# FlatSat-PC-104.net
KiCad netlist of a schematic drawn in Altium Designer
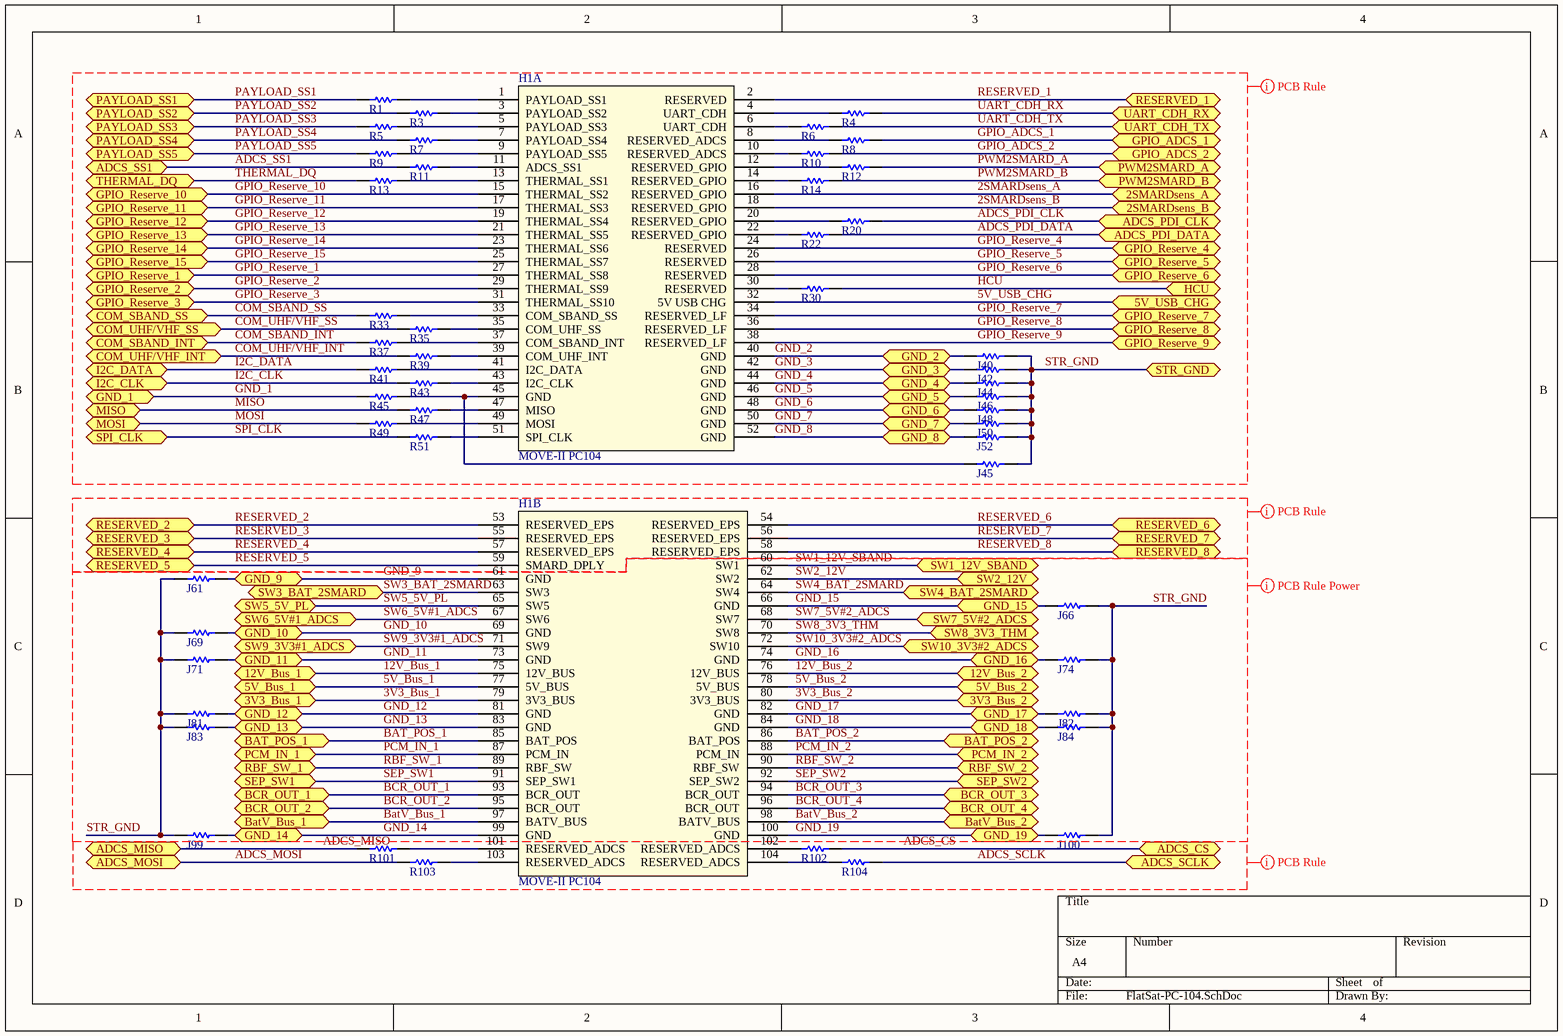
[diagram p0: FlatSat-PC-104.SchDoc]

(export (version "E")
  (design (tool "Eeschema 10.0.6"))
  (components
    (comp (ref "H1")
      (value "MOVE-II PC104")
      (footprint "EPS")
      (libsource (lib "MOVE-II") (part "MOVE-II PC104"))
    )
    (comp (ref "J40")
      (value "CRCW06030000Z0EA")
      (footprint "RESC1609X55X30ML10T20")
      (fields (field (name "MANUFACTURER") "Vishay Dale"))
      (libsource (lib "Altium Content Vault") (part "CMP-2000-03816-1"))
    )
    (comp (ref "J42")
      (value "CRCW06030000Z0EA")
      (footprint "RESC1609X55X30ML10T20")
      (fields (field (name "MANUFACTURER") "Vishay Dale"))
      (libsource (lib "Altium Content Vault") (part "CMP-2000-03816-1"))
    )
    (comp (ref "J44")
      (value "CRCW06030000Z0EA")
      (footprint "RESC1609X55X30ML10T20")
      (fields (field (name "MANUFACTURER") "Vishay Dale"))
      (libsource (lib "Altium Content Vault") (part "CMP-2000-03816-1"))
    )
    (comp (ref "J45")
      (value "CRCW06030000Z0EA")
      (footprint "RESC1609X55X30ML10T20")
      (fields (field (name "MANUFACTURER") "Vishay Dale"))
      (libsource (lib "Altium Content Vault") (part "CMP-2000-03816-1"))
    )
    (comp (ref "J46")
      (value "CRCW06030000Z0EA")
      (footprint "RESC1609X55X30ML10T20")
      (fields (field (name "MANUFACTURER") "Vishay Dale"))
      (libsource (lib "Altium Content Vault") (part "CMP-2000-03816-1"))
    )
    (comp (ref "J48")
      (value "CRCW06030000Z0EA")
      (footprint "RESC1609X55X30ML10T20")
      (fields (field (name "MANUFACTURER") "Vishay Dale"))
      (libsource (lib "Altium Content Vault") (part "CMP-2000-03816-1"))
    )
    (comp (ref "J50")
      (value "CRCW06030000Z0EA")
      (footprint "RESC1609X55X30ML10T20")
      (fields (field (name "MANUFACTURER") "Vishay Dale"))
      (libsource (lib "Altium Content Vault") (part "CMP-2000-03816-1"))
    )
    (comp (ref "J52")
      (value "CRCW06030000Z0EA")
      (footprint "RESC1609X55X30ML10T20")
      (fields (field (name "MANUFACTURER") "Vishay Dale"))
      (libsource (lib "Altium Content Vault") (part "CMP-2000-03816-1"))
    )
    (comp (ref "J61")
      (value "CRCW06030000Z0EA")
      (footprint "RESC1609X55X30ML10T20")
      (fields (field (name "MANUFACTURER") "Vishay Dale"))
      (libsource (lib "Altium Content Vault") (part "CMP-2000-03816-1"))
    )
    (comp (ref "J66")
      (value "CRCW06030000Z0EA")
      (footprint "RESC1609X55X30ML10T20")
      (fields (field (name "MANUFACTURER") "Vishay Dale"))
      (libsource (lib "Altium Content Vault") (part "CMP-2000-03816-1"))
    )
    (comp (ref "J69")
      (value "CRCW06030000Z0EA")
      (footprint "RESC1609X55X30ML10T20")
      (fields (field (name "MANUFACTURER") "Vishay Dale"))
      (libsource (lib "Altium Content Vault") (part "CMP-2000-03816-1"))
    )
    (comp (ref "J71")
      (value "CRCW06030000Z0EA")
      (footprint "RESC1609X55X30ML10T20")
      (fields (field (name "MANUFACTURER") "Vishay Dale"))
      (libsource (lib "Altium Content Vault") (part "CMP-2000-03816-1"))
    )
    (comp (ref "J74")
      (value "CRCW06030000Z0EA")
      (footprint "RESC1609X55X30ML10T20")
      (fields (field (name "MANUFACTURER") "Vishay Dale"))
      (libsource (lib "Altium Content Vault") (part "CMP-2000-03816-1"))
    )
    (comp (ref "J81")
      (value "CRCW06030000Z0EA")
      (footprint "RESC1609X55X30ML10T20")
      (fields (field (name "MANUFACTURER") "Vishay Dale"))
      (libsource (lib "Altium Content Vault") (part "CMP-2000-03816-1"))
    )
    (comp (ref "J82")
      (value "CRCW06030000Z0EA")
      (footprint "RESC1609X55X30ML10T20")
      (fields (field (name "MANUFACTURER") "Vishay Dale"))
      (libsource (lib "Altium Content Vault") (part "CMP-2000-03816-1"))
    )
    (comp (ref "J83")
      (value "CRCW06030000Z0EA")
      (footprint "RESC1609X55X30ML10T20")
      (fields (field (name "MANUFACTURER") "Vishay Dale"))
      (libsource (lib "Altium Content Vault") (part "CMP-2000-03816-1"))
    )
    (comp (ref "J84")
      (value "CRCW06030000Z0EA")
      (footprint "RESC1609X55X30ML10T20")
      (fields (field (name "MANUFACTURER") "Vishay Dale"))
      (libsource (lib "Altium Content Vault") (part "CMP-2000-03816-1"))
    )
    (comp (ref "J99")
      (value "CRCW06030000Z0EA")
      (footprint "RESC1609X55X30ML10T20")
      (fields (field (name "MANUFACTURER") "Vishay Dale"))
      (libsource (lib "Altium Content Vault") (part "CMP-2000-03816-1"))
    )
    (comp (ref "J100")
      (value "CRCW06030000Z0EA")
      (footprint "RESC1609X55X30ML10T20")
      (fields (field (name "MANUFACTURER") "Vishay Dale"))
      (libsource (lib "Altium Content Vault") (part "CMP-2000-03816-1"))
    )
    (comp (ref "R1")
      (value "CRCW06030000Z0EA")
      (footprint "RESC1609X55X30ML10T20")
      (fields (field (name "MANUFACTURER") "Vishay Dale"))
      (libsource (lib "Altium Content Vault") (part "CMP-2000-03816-1"))
    )
    (comp (ref "R3")
      (value "CRCW06030000Z0EA")
      (footprint "RESC1609X55X30ML10T20")
      (fields (field (name "MANUFACTURER") "Vishay Dale"))
      (libsource (lib "Altium Content Vault") (part "CMP-2000-03816-1"))
    )
    (comp (ref "R4")
      (value "CRCW06030000Z0EA")
      (footprint "RESC1609X55X30ML10T20")
      (fields (field (name "MANUFACTURER") "Vishay Dale"))
      (libsource (lib "Altium Content Vault") (part "CMP-2000-03816-1"))
    )
    (comp (ref "R5")
      (value "CRCW06030000Z0EA")
      (footprint "RESC1609X55X30ML10T20")
      (fields (field (name "MANUFACTURER") "Vishay Dale"))
      (libsource (lib "Altium Content Vault") (part "CMP-2000-03816-1"))
    )
    (comp (ref "R6")
      (value "CRCW06030000Z0EA")
      (footprint "RESC1609X55X30ML10T20")
      (fields (field (name "MANUFACTURER") "Vishay Dale"))
      (libsource (lib "Altium Content Vault") (part "CMP-2000-03816-1"))
    )
    (comp (ref "R7")
      (value "CRCW06030000Z0EA")
      (footprint "RESC1609X55X30ML10T20")
      (fields (field (name "MANUFACTURER") "Vishay Dale"))
      (libsource (lib "Altium Content Vault") (part "CMP-2000-03816-1"))
    )
    (comp (ref "R8")
      (value "CRCW06030000Z0EA")
      (footprint "RESC1609X55X30ML10T20")
      (fields (field (name "MANUFACTURER") "Vishay Dale"))
      (libsource (lib "Altium Content Vault") (part "CMP-2000-03816-1"))
    )
    (comp (ref "R9")
      (value "CRCW06030000Z0EA")
      (footprint "RESC1609X55X30ML10T20")
      (fields (field (name "MANUFACTURER") "Vishay Dale"))
      (libsource (lib "Altium Content Vault") (part "CMP-2000-03816-1"))
    )
    (comp (ref "R10")
      (value "CRCW06030000Z0EA")
      (footprint "RESC1609X55X30ML10T20")
      (fields (field (name "MANUFACTURER") "Vishay Dale"))
      (libsource (lib "Altium Content Vault") (part "CMP-2000-03816-1"))
    )
    (comp (ref "R11")
      (value "CRCW06030000Z0EA")
      (footprint "RESC1609X55X30ML10T20")
      (fields (field (name "MANUFACTURER") "Vishay Dale"))
      (libsource (lib "Altium Content Vault") (part "CMP-2000-03816-1"))
    )
    (comp (ref "R12")
      (value "CRCW06030000Z0EA")
      (footprint "RESC1609X55X30ML10T20")
      (fields (field (name "MANUFACTURER") "Vishay Dale"))
      (libsource (lib "Altium Content Vault") (part "CMP-2000-03816-1"))
    )
    (comp (ref "R13")
      (value "CRCW06030000Z0EA")
      (footprint "RESC1609X55X30ML10T20")
      (fields (field (name "MANUFACTURER") "Vishay Dale"))
      (libsource (lib "Altium Content Vault") (part "CMP-2000-03816-1"))
    )
    (comp (ref "R14")
      (value "CRCW06030000Z0EA")
      (footprint "RESC1609X55X30ML10T20")
      (fields (field (name "MANUFACTURER") "Vishay Dale"))
      (libsource (lib "Altium Content Vault") (part "CMP-2000-03816-1"))
    )
    (comp (ref "R20")
      (value "CRCW06030000Z0EA")
      (footprint "RESC1609X55X30ML10T20")
      (fields (field (name "MANUFACTURER") "Vishay Dale"))
      (libsource (lib "Altium Content Vault") (part "CMP-2000-03816-1"))
    )
    (comp (ref "R22")
      (value "CRCW06030000Z0EA")
      (footprint "RESC1609X55X30ML10T20")
      (fields (field (name "MANUFACTURER") "Vishay Dale"))
      (libsource (lib "Altium Content Vault") (part "CMP-2000-03816-1"))
    )
    (comp (ref "R30")
      (value "CRCW06030000Z0EA")
      (footprint "RESC1609X55X30ML10T20")
      (fields (field (name "MANUFACTURER") "Vishay Dale"))
      (libsource (lib "Altium Content Vault") (part "CMP-2000-03816-1"))
    )
    (comp (ref "R33")
      (value "CRCW06030000Z0EA")
      (footprint "RESC1609X55X30ML10T20")
      (fields (field (name "MANUFACTURER") "Vishay Dale"))
      (libsource (lib "Altium Content Vault") (part "CMP-2000-03816-1"))
    )
    (comp (ref "R35")
      (value "CRCW06030000Z0EA")
      (footprint "RESC1609X55X30ML10T20")
      (fields (field (name "MANUFACTURER") "Vishay Dale"))
      (libsource (lib "Altium Content Vault") (part "CMP-2000-03816-1"))
    )
    (comp (ref "R37")
      (value "CRCW06030000Z0EA")
      (footprint "RESC1609X55X30ML10T20")
      (fields (field (name "MANUFACTURER") "Vishay Dale"))
      (libsource (lib "Altium Content Vault") (part "CMP-2000-03816-1"))
    )
    (comp (ref "R39")
      (value "CRCW06030000Z0EA")
      (footprint "RESC1609X55X30ML10T20")
      (fields (field (name "MANUFACTURER") "Vishay Dale"))
      (libsource (lib "Altium Content Vault") (part "CMP-2000-03816-1"))
    )
    (comp (ref "R41")
      (value "CRCW06030000Z0EA")
      (footprint "RESC1609X55X30ML10T20")
      (fields (field (name "MANUFACTURER") "Vishay Dale"))
      (libsource (lib "Altium Content Vault") (part "CMP-2000-03816-1"))
    )
    (comp (ref "R43")
      (value "CRCW06030000Z0EA")
      (footprint "RESC1609X55X30ML10T20")
      (fields (field (name "MANUFACTURER") "Vishay Dale"))
      (libsource (lib "Altium Content Vault") (part "CMP-2000-03816-1"))
    )
    (comp (ref "R45")
      (value "CRCW06030000Z0EA")
      (footprint "RESC1609X55X30ML10T20")
      (fields (field (name "MANUFACTURER") "Vishay Dale"))
      (libsource (lib "Altium Content Vault") (part "CMP-2000-03816-1"))
    )
    (comp (ref "R47")
      (value "CRCW06030000Z0EA")
      (footprint "RESC1609X55X30ML10T20")
      (fields (field (name "MANUFACTURER") "Vishay Dale"))
      (libsource (lib "Altium Content Vault") (part "CMP-2000-03816-1"))
    )
    (comp (ref "R49")
      (value "CRCW06030000Z0EA")
      (footprint "RESC1609X55X30ML10T20")
      (fields (field (name "MANUFACTURER") "Vishay Dale"))
      (libsource (lib "Altium Content Vault") (part "CMP-2000-03816-1"))
    )
    (comp (ref "R51")
      (value "CRCW06030000Z0EA")
      (footprint "RESC1609X55X30ML10T20")
      (fields (field (name "MANUFACTURER") "Vishay Dale"))
      (libsource (lib "Altium Content Vault") (part "CMP-2000-03816-1"))
    )
    (comp (ref "R101")
      (value "CRCW06030000Z0EA")
      (footprint "RESC1609X55X30ML10T20")
      (fields (field (name "MANUFACTURER") "Vishay Dale"))
      (libsource (lib "Altium Content Vault") (part "CMP-2000-03816-1"))
    )
    (comp (ref "R102")
      (value "CRCW06030000Z0EA")
      (footprint "RESC1609X55X30ML10T20")
      (fields (field (name "MANUFACTURER") "Vishay Dale"))
      (libsource (lib "Altium Content Vault") (part "CMP-2000-03816-1"))
    )
    (comp (ref "R103")
      (value "CRCW06030000Z0EA")
      (footprint "RESC1609X55X30ML10T20")
      (fields (field (name "MANUFACTURER") "Vishay Dale"))
      (libsource (lib "Altium Content Vault") (part "CMP-2000-03816-1"))
    )
    (comp (ref "R104")
      (value "CRCW06030000Z0EA")
      (footprint "RESC1609X55X30ML10T20")
      (fields (field (name "MANUFACTURER") "Vishay Dale"))
      (libsource (lib "Altium Content Vault") (part "CMP-2000-03816-1"))
    )
  )
  (nets
    (net (code "1") (name "/2SMARDsens_A") (class "Default")
      (node (ref "H1") (pin "16") (pinfunction "RESERVED_GPIO_16") (pintype "passive"))
    )
    (net (code "2") (name "/2SMARDsens_B") (class "Default")
      (node (ref "H1") (pin "18") (pinfunction "RESERVED_GPIO_18") (pintype "passive"))
    )
    (net (code "3") (name "/3V3_Bus_1") (class "Default")
      (node (ref "H1") (pin "79") (pinfunction "3V3_BUS_79") (pintype "passive"))
    )
    (net (code "4") (name "/3V3_Bus_2") (class "Default")
      (node (ref "H1") (pin "80") (pinfunction "3V3_BUS_80") (pintype "passive"))
    )
    (net (code "5") (name "/5V_Bus_1") (class "Default")
      (node (ref "H1") (pin "77") (pinfunction "5V_BUS_77") (pintype "passive"))
    )
    (net (code "6") (name "/5V_Bus_2") (class "Default")
      (node (ref "H1") (pin "78") (pinfunction "5V_BUS_78") (pintype "passive"))
    )
    (net (code "7") (name "/5V_USB_CHG") (class "Default")
      (node (ref "H1") (pin "32") (pinfunction "5V_USB_CHG_32") (pintype "passive"))
    )
    (net (code "8") (name "/12V_Bus_1") (class "Default")
      (node (ref "H1") (pin "75") (pinfunction "12V_BUS_75") (pintype "passive"))
    )
    (net (code "9") (name "/12V_Bus_2") (class "Default")
      (node (ref "H1") (pin "76") (pinfunction "12V_BUS_76") (pintype "passive"))
    )
    (net (code "10") (name "/ADCS_CS") (class "Default")
      (node (ref "R102") (pin "1") (pinfunction "1_1") (pintype "passive"))
    )
    (net (code "11") (name "/ADCS_MISO") (class "Default")
      (node (ref "R101") (pin "2") (pinfunction "2_2") (pintype "passive"))
    )
    (net (code "12") (name "/ADCS_MOSI") (class "Default")
      (node (ref "R103") (pin "1") (pinfunction "1_1") (pintype "passive"))
    )
    (net (code "13") (name "/ADCS_PDI_CLK") (class "Default")
      (node (ref "R20") (pin "2") (pinfunction "2_2") (pintype "passive"))
    )
    (net (code "14") (name "/ADCS_PDI_DATA") (class "Default")
      (node (ref "R22") (pin "2") (pinfunction "2_2") (pintype "passive"))
    )
    (net (code "15") (name "/ADCS_SCLK") (class "Default")
      (node (ref "R104") (pin "2") (pinfunction "2_2") (pintype "passive"))
    )
    (net (code "16") (name "/ADCS_SS1") (class "Default")
      (node (ref "R11") (pin "1") (pinfunction "1_1") (pintype "passive"))
    )
    (net (code "17") (name "/BAT_POS_1") (class "Default")
      (node (ref "H1") (pin "85") (pinfunction "BAT_POS_85") (pintype "passive"))
    )
    (net (code "18") (name "/BAT_POS_2") (class "Default")
      (node (ref "H1") (pin "86") (pinfunction "BAT_POS_86") (pintype "passive"))
    )
    (net (code "19") (name "/BCR_OUT_1") (class "Default")
      (node (ref "H1") (pin "93") (pinfunction "BCR_OUT_93") (pintype "passive"))
    )
    (net (code "20") (name "/BCR_OUT_2") (class "Default")
      (node (ref "H1") (pin "95") (pinfunction "BCR_OUT_95") (pintype "passive"))
    )
    (net (code "21") (name "/BCR_OUT_3") (class "Default")
      (node (ref "H1") (pin "94") (pinfunction "BCR_OUT_94") (pintype "passive"))
    )
    (net (code "22") (name "/BCR_OUT_4") (class "Default")
      (node (ref "H1") (pin "96") (pinfunction "BCR_OUT_96") (pintype "passive"))
    )
    (net (code "23") (name "/BatV_Bus_1") (class "Default")
      (node (ref "H1") (pin "97") (pinfunction "BATV_BUS_97") (pintype "passive"))
    )
    (net (code "24") (name "/BatV_Bus_2") (class "Default")
      (node (ref "H1") (pin "98") (pinfunction "BATV_BUS_98") (pintype "passive"))
    )
    (net (code "25") (name "/COM_SBAND_INT") (class "Default")
      (node (ref "R37") (pin "1") (pinfunction "1_1") (pintype "passive"))
    )
    (net (code "26") (name "/COM_SBAND_SS") (class "Default")
      (node (ref "R33") (pin "1") (pinfunction "1_1") (pintype "passive"))
    )
    (net (code "27") (name "/COM_UHF{slash}VHF_INT") (class "Default")
      (node (ref "R39") (pin "1") (pinfunction "1_1") (pintype "passive"))
    )
    (net (code "28") (name "/COM_UHF{slash}VHF_SS") (class "Default")
      (node (ref "R35") (pin "2") (pinfunction "2_2") (pintype "passive"))
    )
    (net (code "29") (name "/GND_1") (class "Default")
      (node (ref "R45") (pin "1") (pinfunction "1_1") (pintype "passive"))
    )
    (net (code "30") (name "/GND_2") (class "Default")
      (node (ref "H1") (pin "40") (pinfunction "GND_40") (pintype "passive"))
      (node (ref "J40") (pin "1") (pinfunction "1_1") (pintype "passive"))
    )
    (net (code "31") (name "/GND_3") (class "Default")
      (node (ref "H1") (pin "42") (pinfunction "GND_42") (pintype "passive"))
      (node (ref "J42") (pin "1") (pinfunction "1_1") (pintype "passive"))
    )
    (net (code "32") (name "/GND_4") (class "Default")
      (node (ref "H1") (pin "44") (pinfunction "GND_44") (pintype "passive"))
      (node (ref "J44") (pin "1") (pinfunction "1_1") (pintype "passive"))
    )
    (net (code "33") (name "/GND_5") (class "Default")
      (node (ref "H1") (pin "46") (pinfunction "GND_46") (pintype "passive"))
      (node (ref "J46") (pin "1") (pinfunction "1_1") (pintype "passive"))
    )
    (net (code "34") (name "/GND_6") (class "Default")
      (node (ref "H1") (pin "48") (pinfunction "GND_48") (pintype "passive"))
      (node (ref "J48") (pin "1") (pinfunction "1_1") (pintype "passive"))
    )
    (net (code "35") (name "/GND_7") (class "Default")
      (node (ref "H1") (pin "50") (pinfunction "GND_50") (pintype "passive"))
      (node (ref "J50") (pin "1") (pinfunction "1_1") (pintype "passive"))
    )
    (net (code "36") (name "/GND_8") (class "Default")
      (node (ref "H1") (pin "52") (pinfunction "GND_52") (pintype "passive"))
      (node (ref "J52") (pin "1") (pinfunction "1_1") (pintype "passive"))
    )
    (net (code "37") (name "/GND_9") (class "Default")
      (node (ref "H1") (pin "61") (pinfunction "GND_61") (pintype "passive"))
      (node (ref "J61") (pin "2") (pinfunction "2_2") (pintype "passive"))
    )
    (net (code "38") (name "/GND_10") (class "Default")
      (node (ref "H1") (pin "69") (pinfunction "GND_69") (pintype "passive"))
      (node (ref "J69") (pin "2") (pinfunction "2_2") (pintype "passive"))
    )
    (net (code "39") (name "/GND_11") (class "Default")
      (node (ref "H1") (pin "73") (pinfunction "GND_73") (pintype "passive"))
      (node (ref "J71") (pin "2") (pinfunction "2_2") (pintype "passive"))
    )
    (net (code "40") (name "/GND_12") (class "Default")
      (node (ref "H1") (pin "81") (pinfunction "GND_81") (pintype "passive"))
      (node (ref "J81") (pin "2") (pinfunction "2_2") (pintype "passive"))
    )
    (net (code "41") (name "/GND_13") (class "Default")
      (node (ref "H1") (pin "83") (pinfunction "GND_83") (pintype "passive"))
      (node (ref "J83") (pin "2") (pinfunction "2_2") (pintype "passive"))
    )
    (net (code "42") (name "/GND_14") (class "Default")
      (node (ref "H1") (pin "99") (pinfunction "GND_99") (pintype "passive"))
      (node (ref "J99") (pin "2") (pinfunction "2_2") (pintype "passive"))
    )
    (net (code "43") (name "/GND_15") (class "Default")
      (node (ref "H1") (pin "66") (pinfunction "GND_66") (pintype "passive"))
      (node (ref "J66") (pin "1") (pinfunction "1_1") (pintype "passive"))
    )
    (net (code "44") (name "/GND_16") (class "Default")
      (node (ref "H1") (pin "74") (pinfunction "GND_74") (pintype "passive"))
      (node (ref "J74") (pin "1") (pinfunction "1_1") (pintype "passive"))
    )
    (net (code "45") (name "/GND_17") (class "Default")
      (node (ref "H1") (pin "82") (pinfunction "GND_82") (pintype "passive"))
      (node (ref "J82") (pin "1") (pinfunction "1_1") (pintype "passive"))
    )
    (net (code "46") (name "/GND_18") (class "Default")
      (node (ref "H1") (pin "84") (pinfunction "GND_84") (pintype "passive"))
      (node (ref "J84") (pin "1") (pinfunction "1_1") (pintype "passive"))
    )
    (net (code "47") (name "/GND_19") (class "Default")
      (node (ref "H1") (pin "100") (pinfunction "GND_100") (pintype "passive"))
      (node (ref "J100") (pin "1") (pinfunction "1_1") (pintype "passive"))
    )
    (net (code "48") (name "/GPIO_ADCS_1") (class "Default")
      (node (ref "R8") (pin "2") (pinfunction "2_2") (pintype "passive"))
    )
    (net (code "49") (name "/GPIO_ADCS_2") (class "Default")
      (node (ref "R10") (pin "2") (pinfunction "2_2") (pintype "passive"))
    )
    (net (code "50") (name "/GPIO_Reserve_1") (class "Default")
      (node (ref "H1") (pin "27") (pinfunction "THERMAL_SS8_27") (pintype "passive"))
    )
    (net (code "51") (name "/GPIO_Reserve_2") (class "Default")
      (node (ref "H1") (pin "29") (pinfunction "THERMAL_SS9_29") (pintype "passive"))
    )
    (net (code "52") (name "/GPIO_Reserve_3") (class "Default")
      (node (ref "H1") (pin "31") (pinfunction "THERMAL_SS10_31") (pintype "passive"))
    )
    (net (code "53") (name "/GPIO_Reserve_4") (class "Default")
      (node (ref "H1") (pin "24") (pinfunction "RESERVED_24") (pintype "passive"))
    )
    (net (code "54") (name "/GPIO_Reserve_5") (class "Default")
      (node (ref "H1") (pin "26") (pinfunction "RESERVED_26") (pintype "passive"))
    )
    (net (code "55") (name "/GPIO_Reserve_6") (class "Default")
      (node (ref "H1") (pin "28") (pinfunction "RESERVED_28") (pintype "passive"))
    )
    (net (code "56") (name "/GPIO_Reserve_7") (class "Default")
      (node (ref "H1") (pin "34") (pinfunction "RESERVED_LF_34") (pintype "passive"))
    )
    (net (code "57") (name "/GPIO_Reserve_8") (class "Default")
      (node (ref "H1") (pin "36") (pinfunction "RESERVED_LF_36") (pintype "passive"))
    )
    (net (code "58") (name "/GPIO_Reserve_9") (class "Default")
      (node (ref "H1") (pin "38") (pinfunction "RESERVED_LF_38") (pintype "passive"))
    )
    (net (code "59") (name "/GPIO_Reserve_10") (class "Default")
      (node (ref "H1") (pin "15") (pinfunction "THERMAL_SS2_15") (pintype "passive"))
    )
    (net (code "60") (name "/GPIO_Reserve_11") (class "Default")
      (node (ref "H1") (pin "17") (pinfunction "THERMAL_SS3_17") (pintype "passive"))
    )
    (net (code "61") (name "/GPIO_Reserve_12") (class "Default")
      (node (ref "H1") (pin "19") (pinfunction "THERMAL_SS4_19") (pintype "passive"))
    )
    (net (code "62") (name "/GPIO_Reserve_13") (class "Default")
      (node (ref "H1") (pin "21") (pinfunction "THERMAL_SS5_21") (pintype "passive"))
    )
    (net (code "63") (name "/GPIO_Reserve_14") (class "Default")
      (node (ref "H1") (pin "23") (pinfunction "THERMAL_SS6_23") (pintype "passive"))
    )
    (net (code "64") (name "/GPIO_Reserve_15") (class "Default")
      (node (ref "H1") (pin "25") (pinfunction "THERMAL_SS7_25") (pintype "passive"))
    )
    (net (code "65") (name "/HCU") (class "Default")
      (node (ref "R30") (pin "2") (pinfunction "2_2") (pintype "passive"))
    )
    (net (code "66") (name "/I2C_CLK") (class "Default")
      (node (ref "R43") (pin "1") (pinfunction "1_1") (pintype "passive"))
    )
    (net (code "67") (name "/I2C_DATA") (class "Default")
      (node (ref "R41") (pin "1") (pinfunction "1_1") (pintype "passive"))
    )
    (net (code "68") (name "/MISO") (class "Default")
      (node (ref "R47") (pin "1") (pinfunction "1_1") (pintype "passive"))
    )
    (net (code "69") (name "/MOSI") (class "Default")
      (node (ref "R49") (pin "1") (pinfunction "1_1") (pintype "passive"))
    )
    (net (code "70") (name "/PAYLOAD_SS1") (class "Default")
      (node (ref "R1") (pin "1") (pinfunction "1_1") (pintype "passive"))
    )
    (net (code "71") (name "/PAYLOAD_SS2") (class "Default")
      (node (ref "R3") (pin "1") (pinfunction "1_1") (pintype "passive"))
    )
    (net (code "72") (name "/PAYLOAD_SS3") (class "Default")
      (node (ref "R5") (pin "1") (pinfunction "1_1") (pintype "passive"))
    )
    (net (code "73") (name "/PAYLOAD_SS4") (class "Default")
      (node (ref "R7") (pin "1") (pinfunction "1_1") (pintype "passive"))
    )
    (net (code "74") (name "/PAYLOAD_SS5") (class "Default")
      (node (ref "R9") (pin "1") (pinfunction "1_1") (pintype "passive"))
    )
    (net (code "75") (name "/PCM_IN_1") (class "Default")
      (node (ref "H1") (pin "87") (pinfunction "PCM_IN_87") (pintype "passive"))
    )
    (net (code "76") (name "/PCM_IN_2") (class "Default")
      (node (ref "H1") (pin "88") (pinfunction "PCM_IN_88") (pintype "passive"))
    )
    (net (code "77") (name "/PWM2SMARD_A") (class "Default")
      (node (ref "R12") (pin "2") (pinfunction "2_2") (pintype "passive"))
    )
    (net (code "78") (name "/PWM2SMARD_B") (class "Default")
      (node (ref "R14") (pin "2") (pinfunction "2_2") (pintype "passive"))
    )
    (net (code "79") (name "/RBF_SW_1") (class "Default")
      (node (ref "H1") (pin "89") (pinfunction "RBF_SW_89") (pintype "passive"))
    )
    (net (code "80") (name "/RBF_SW_2") (class "Default")
      (node (ref "H1") (pin "90") (pinfunction "RBF_SW_90") (pintype "passive"))
    )
    (net (code "81") (name "/RESERVED_1") (class "Default")
      (node (ref "H1") (pin "2") (pinfunction "RESERVED_2") (pintype "passive"))
    )
    (net (code "82") (name "/RESERVED_2") (class "Default")
      (node (ref "H1") (pin "53") (pinfunction "RESERVED_EPS_53") (pintype "passive"))
    )
    (net (code "83") (name "/RESERVED_3") (class "Default")
      (node (ref "H1") (pin "55") (pinfunction "RESERVED_EPS_55") (pintype "passive"))
    )
    (net (code "84") (name "/RESERVED_4") (class "Default")
      (node (ref "H1") (pin "57") (pinfunction "RESERVED_EPS_57") (pintype "passive"))
    )
    (net (code "85") (name "/RESERVED_5") (class "Default")
      (node (ref "H1") (pin "59") (pinfunction "SMARD_DPLY_59") (pintype "passive"))
    )
    (net (code "86") (name "/RESERVED_6") (class "Default")
      (node (ref "H1") (pin "54") (pinfunction "RESERVED_EPS_54") (pintype "passive"))
    )
    (net (code "87") (name "/RESERVED_7") (class "Default")
      (node (ref "H1") (pin "56") (pinfunction "RESERVED_EPS_56") (pintype "passive"))
    )
    (net (code "88") (name "/RESERVED_8") (class "Default")
      (node (ref "H1") (pin "58") (pinfunction "RESERVED_EPS_58") (pintype "passive"))
    )
    (net (code "89") (name "/SEP_SW1") (class "Default")
      (node (ref "H1") (pin "91") (pinfunction "SEP_SW1_91") (pintype "passive"))
    )
    (net (code "90") (name "/SEP_SW2") (class "Default")
      (node (ref "H1") (pin "92") (pinfunction "SEP_SW2_92") (pintype "passive"))
    )
    (net (code "91") (name "/SPI_CLK") (class "Default")
      (node (ref "R51") (pin "1") (pinfunction "1_1") (pintype "passive"))
    )
    (net (code "92") (name "/STR_GND") (class "Default")
      (node (ref "J100") (pin "2") (pinfunction "2_2") (pintype "passive"))
      (node (ref "J40") (pin "2") (pinfunction "2_2") (pintype "passive"))
      (node (ref "J42") (pin "2") (pinfunction "2_2") (pintype "passive"))
      (node (ref "J44") (pin "2") (pinfunction "2_2") (pintype "passive"))
      (node (ref "J45") (pin "2") (pinfunction "2_2") (pintype "passive"))
      (node (ref "J46") (pin "2") (pinfunction "2_2") (pintype "passive"))
      (node (ref "J48") (pin "2") (pinfunction "2_2") (pintype "passive"))
      (node (ref "J50") (pin "2") (pinfunction "2_2") (pintype "passive"))
      (node (ref "J52") (pin "2") (pinfunction "2_2") (pintype "passive"))
      (node (ref "J61") (pin "1") (pinfunction "1_1") (pintype "passive"))
      (node (ref "J66") (pin "2") (pinfunction "2_2") (pintype "passive"))
      (node (ref "J69") (pin "1") (pinfunction "1_1") (pintype "passive"))
      (node (ref "J71") (pin "1") (pinfunction "1_1") (pintype "passive"))
      (node (ref "J74") (pin "2") (pinfunction "2_2") (pintype "passive"))
      (node (ref "J81") (pin "1") (pinfunction "1_1") (pintype "passive"))
      (node (ref "J82") (pin "2") (pinfunction "2_2") (pintype "passive"))
      (node (ref "J83") (pin "1") (pinfunction "1_1") (pintype "passive"))
      (node (ref "J84") (pin "2") (pinfunction "2_2") (pintype "passive"))
      (node (ref "J99") (pin "1") (pinfunction "1_1") (pintype "passive"))
    )
    (net (code "93") (name "/SW1_12V_SBAND") (class "Default")
      (node (ref "H1") (pin "60") (pinfunction "SW1_60") (pintype "passive"))
    )
    (net (code "94") (name "/SW2_12V") (class "Default")
      (node (ref "H1") (pin "62") (pinfunction "SW2_62") (pintype "passive"))
    )
    (net (code "95") (name "/SW3_BAT_2SMARD") (class "Default")
      (node (ref "H1") (pin "63") (pinfunction "SW3_63") (pintype "passive"))
    )
    (net (code "96") (name "/SW4_BAT_2SMARD") (class "Default")
      (node (ref "H1") (pin "64") (pinfunction "SW4_64") (pintype "passive"))
    )
    (net (code "97") (name "/SW5_5V_PL") (class "Default")
      (node (ref "H1") (pin "65") (pinfunction "SW5_65") (pintype "passive"))
    )
    (net (code "98") (name "/SW6_5V#1_ADCS") (class "Default")
      (node (ref "H1") (pin "67") (pinfunction "SW6_67") (pintype "passive"))
    )
    (net (code "99") (name "/SW7_5V#2_ADCS") (class "Default")
      (node (ref "H1") (pin "68") (pinfunction "SW7_68") (pintype "passive"))
    )
    (net (code "100") (name "/SW8_3V3_THM") (class "Default")
      (node (ref "H1") (pin "70") (pinfunction "SW8_70") (pintype "passive"))
    )
    (net (code "101") (name "/SW9_3V3#1_ADCS") (class "Default")
      (node (ref "H1") (pin "71") (pinfunction "SW9_71") (pintype "passive"))
    )
    (net (code "102") (name "/SW10_3V3#2_ADCS") (class "Default")
      (node (ref "H1") (pin "72") (pinfunction "SW10_72") (pintype "passive"))
    )
    (net (code "103") (name "/THERMAL_DQ") (class "Default")
      (node (ref "R13") (pin "1") (pinfunction "1_1") (pintype "passive"))
    )
    (net (code "104") (name "/UART_CDH_RX") (class "Default")
      (node (ref "R4") (pin "2") (pinfunction "2_2") (pintype "passive"))
    )
    (net (code "105") (name "/UART_CDH_TX") (class "Default")
      (node (ref "R6") (pin "2") (pinfunction "2_2") (pintype "passive"))
    )
    (net (code "106") (name "Net-(H1A-ADCS_SS1)") (class "Default")
      (node (ref "H1") (pin "11") (pinfunction "ADCS_SS1_11") (pintype "passive"))
      (node (ref "R11") (pin "2") (pinfunction "2_2") (pintype "passive"))
    )
    (net (code "107") (name "Net-(H1A-COM_SBAND_INT)") (class "Default")
      (node (ref "H1") (pin "37") (pinfunction "COM_SBAND_INT_37") (pintype "passive"))
      (node (ref "R37") (pin "2") (pinfunction "2_2") (pintype "passive"))
    )
    (net (code "108") (name "Net-(H1A-COM_SBAND_SS)") (class "Default")
      (node (ref "H1") (pin "33") (pinfunction "COM_SBAND_SS_33") (pintype "passive"))
      (node (ref "R33") (pin "2") (pinfunction "2_2") (pintype "passive"))
    )
    (net (code "109") (name "Net-(H1A-COM_UHF_INT)") (class "Default")
      (node (ref "H1") (pin "39") (pinfunction "COM_UHF_INT_39") (pintype "passive"))
      (node (ref "R39") (pin "2") (pinfunction "2_2") (pintype "passive"))
    )
    (net (code "110") (name "Net-(H1A-COM_UHF_SS)") (class "Default")
      (node (ref "H1") (pin "35") (pinfunction "COM_UHF_SS_35") (pintype "passive"))
      (node (ref "R35") (pin "1") (pinfunction "1_1") (pintype "passive"))
    )
    (net (code "111") (name "Net-(H1A-GND-Pad45)") (class "Default")
      (node (ref "H1") (pin "45") (pinfunction "GND_45") (pintype "passive"))
      (node (ref "J45") (pin "1") (pinfunction "1_1") (pintype "passive"))
      (node (ref "R45") (pin "2") (pinfunction "2_2") (pintype "passive"))
    )
    (net (code "112") (name "Net-(H1A-I2C_CLK)") (class "Default")
      (node (ref "H1") (pin "43") (pinfunction "I2C_CLK_43") (pintype "passive"))
      (node (ref "R43") (pin "2") (pinfunction "2_2") (pintype "passive"))
    )
    (net (code "113") (name "Net-(H1A-I2C_DATA)") (class "Default")
      (node (ref "H1") (pin "41") (pinfunction "I2C_DATA_41") (pintype "passive"))
      (node (ref "R41") (pin "2") (pinfunction "2_2") (pintype "passive"))
    )
    (net (code "114") (name "Net-(H1A-MISO)") (class "Default")
      (node (ref "H1") (pin "47") (pinfunction "MISO_47") (pintype "passive"))
      (node (ref "R47") (pin "2") (pinfunction "2_2") (pintype "passive"))
    )
    (net (code "115") (name "Net-(H1A-MOSI)") (class "Default")
      (node (ref "H1") (pin "49") (pinfunction "MOSI_49") (pintype "passive"))
      (node (ref "R49") (pin "2") (pinfunction "2_2") (pintype "passive"))
    )
    (net (code "116") (name "Net-(H1A-PAYLOAD_SS1)") (class "Default")
      (node (ref "H1") (pin "1") (pinfunction "PAYLOAD_SS1_1") (pintype "passive"))
      (node (ref "R1") (pin "2") (pinfunction "2_2") (pintype "passive"))
    )
    (net (code "117") (name "Net-(H1A-PAYLOAD_SS2)") (class "Default")
      (node (ref "H1") (pin "3") (pinfunction "PAYLOAD_SS2_3") (pintype "passive"))
      (node (ref "R3") (pin "2") (pinfunction "2_2") (pintype "passive"))
    )
    (net (code "118") (name "Net-(H1A-PAYLOAD_SS3)") (class "Default")
      (node (ref "H1") (pin "5") (pinfunction "PAYLOAD_SS3_5") (pintype "passive"))
      (node (ref "R5") (pin "2") (pinfunction "2_2") (pintype "passive"))
    )
    (net (code "119") (name "Net-(H1A-PAYLOAD_SS4)") (class "Default")
      (node (ref "H1") (pin "7") (pinfunction "PAYLOAD_SS4_7") (pintype "passive"))
      (node (ref "R7") (pin "2") (pinfunction "2_2") (pintype "passive"))
    )
    (net (code "120") (name "Net-(H1A-PAYLOAD_SS5)") (class "Default")
      (node (ref "H1") (pin "9") (pinfunction "PAYLOAD_SS5_9") (pintype "passive"))
      (node (ref "R9") (pin "2") (pinfunction "2_2") (pintype "passive"))
    )
    (net (code "121") (name "Net-(H1A-RESERVED-Pad30)") (class "Default")
      (node (ref "H1") (pin "30") (pinfunction "RESERVED_30") (pintype "passive"))
      (node (ref "R30") (pin "1") (pinfunction "1_1") (pintype "passive"))
    )
    (net (code "122") (name "Net-(H1A-RESERVED_ADCS-Pad8)") (class "Default")
      (node (ref "H1") (pin "8") (pinfunction "RESERVED_ADCS_8") (pintype "passive"))
      (node (ref "R8") (pin "1") (pinfunction "1_1") (pintype "passive"))
    )
    (net (code "123") (name "Net-(H1A-RESERVED_ADCS-Pad10)") (class "Default")
      (node (ref "H1") (pin "10") (pinfunction "RESERVED_ADCS_10") (pintype "passive"))
      (node (ref "R10") (pin "1") (pinfunction "1_1") (pintype "passive"))
    )
    (net (code "124") (name "Net-(H1A-RESERVED_GPIO-Pad12)") (class "Default")
      (node (ref "H1") (pin "12") (pinfunction "RESERVED_GPIO_12") (pintype "passive"))
      (node (ref "R12") (pin "1") (pinfunction "1_1") (pintype "passive"))
    )
    (net (code "125") (name "Net-(H1A-RESERVED_GPIO-Pad14)") (class "Default")
      (node (ref "H1") (pin "14") (pinfunction "RESERVED_GPIO_14") (pintype "passive"))
      (node (ref "R14") (pin "1") (pinfunction "1_1") (pintype "passive"))
    )
    (net (code "126") (name "Net-(H1A-RESERVED_GPIO-Pad20)") (class "Default")
      (node (ref "H1") (pin "20") (pinfunction "RESERVED_GPIO_20") (pintype "passive"))
      (node (ref "R20") (pin "1") (pinfunction "1_1") (pintype "passive"))
    )
    (net (code "127") (name "Net-(H1A-RESERVED_GPIO-Pad22)") (class "Default")
      (node (ref "H1") (pin "22") (pinfunction "RESERVED_GPIO_22") (pintype "passive"))
      (node (ref "R22") (pin "1") (pinfunction "1_1") (pintype "passive"))
    )
    (net (code "128") (name "Net-(H1A-SPI_CLK)") (class "Default")
      (node (ref "H1") (pin "51") (pinfunction "SPI_CLK_51") (pintype "passive"))
      (node (ref "R51") (pin "2") (pinfunction "2_2") (pintype "passive"))
    )
    (net (code "129") (name "Net-(H1A-THERMAL_SS1)") (class "Default")
      (node (ref "H1") (pin "13") (pinfunction "THERMAL_SS1_13") (pintype "passive"))
      (node (ref "R13") (pin "2") (pinfunction "2_2") (pintype "passive"))
    )
    (net (code "130") (name "Net-(H1A-UART_CDH-Pad4)") (class "Default")
      (node (ref "H1") (pin "4") (pinfunction "UART_CDH_4") (pintype "passive"))
      (node (ref "R4") (pin "1") (pinfunction "1_1") (pintype "passive"))
    )
    (net (code "131") (name "Net-(H1A-UART_CDH-Pad6)") (class "Default")
      (node (ref "H1") (pin "6") (pinfunction "UART_CDH_6") (pintype "passive"))
      (node (ref "R6") (pin "1") (pinfunction "1_1") (pintype "passive"))
    )
    (net (code "132") (name "Net-(H1B-RESERVED_ADCS-Pad101)") (class "Default")
      (node (ref "H1") (pin "101") (pinfunction "RESERVED_ADCS_101") (pintype "passive"))
      (node (ref "R101") (pin "1") (pinfunction "1_1") (pintype "passive"))
    )
    (net (code "133") (name "Net-(H1B-RESERVED_ADCS-Pad102)") (class "Default")
      (node (ref "H1") (pin "102") (pinfunction "RESERVED_ADCS_102") (pintype "passive"))
      (node (ref "R102") (pin "2") (pinfunction "2_2") (pintype "passive"))
    )
    (net (code "134") (name "Net-(H1B-RESERVED_ADCS-Pad103)") (class "Default")
      (node (ref "H1") (pin "103") (pinfunction "RESERVED_ADCS_103") (pintype "passive"))
      (node (ref "R103") (pin "2") (pinfunction "2_2") (pintype "passive"))
    )
    (net (code "135") (name "Net-(H1B-RESERVED_ADCS-Pad104)") (class "Default")
      (node (ref "H1") (pin "104") (pinfunction "RESERVED_ADCS_104") (pintype "passive"))
      (node (ref "R104") (pin "1") (pinfunction "1_1") (pintype "passive"))
    )
  )
)
